# CH32V205RCT-R0.net
KiCad netlist of a schematic drawn in Altium Designer
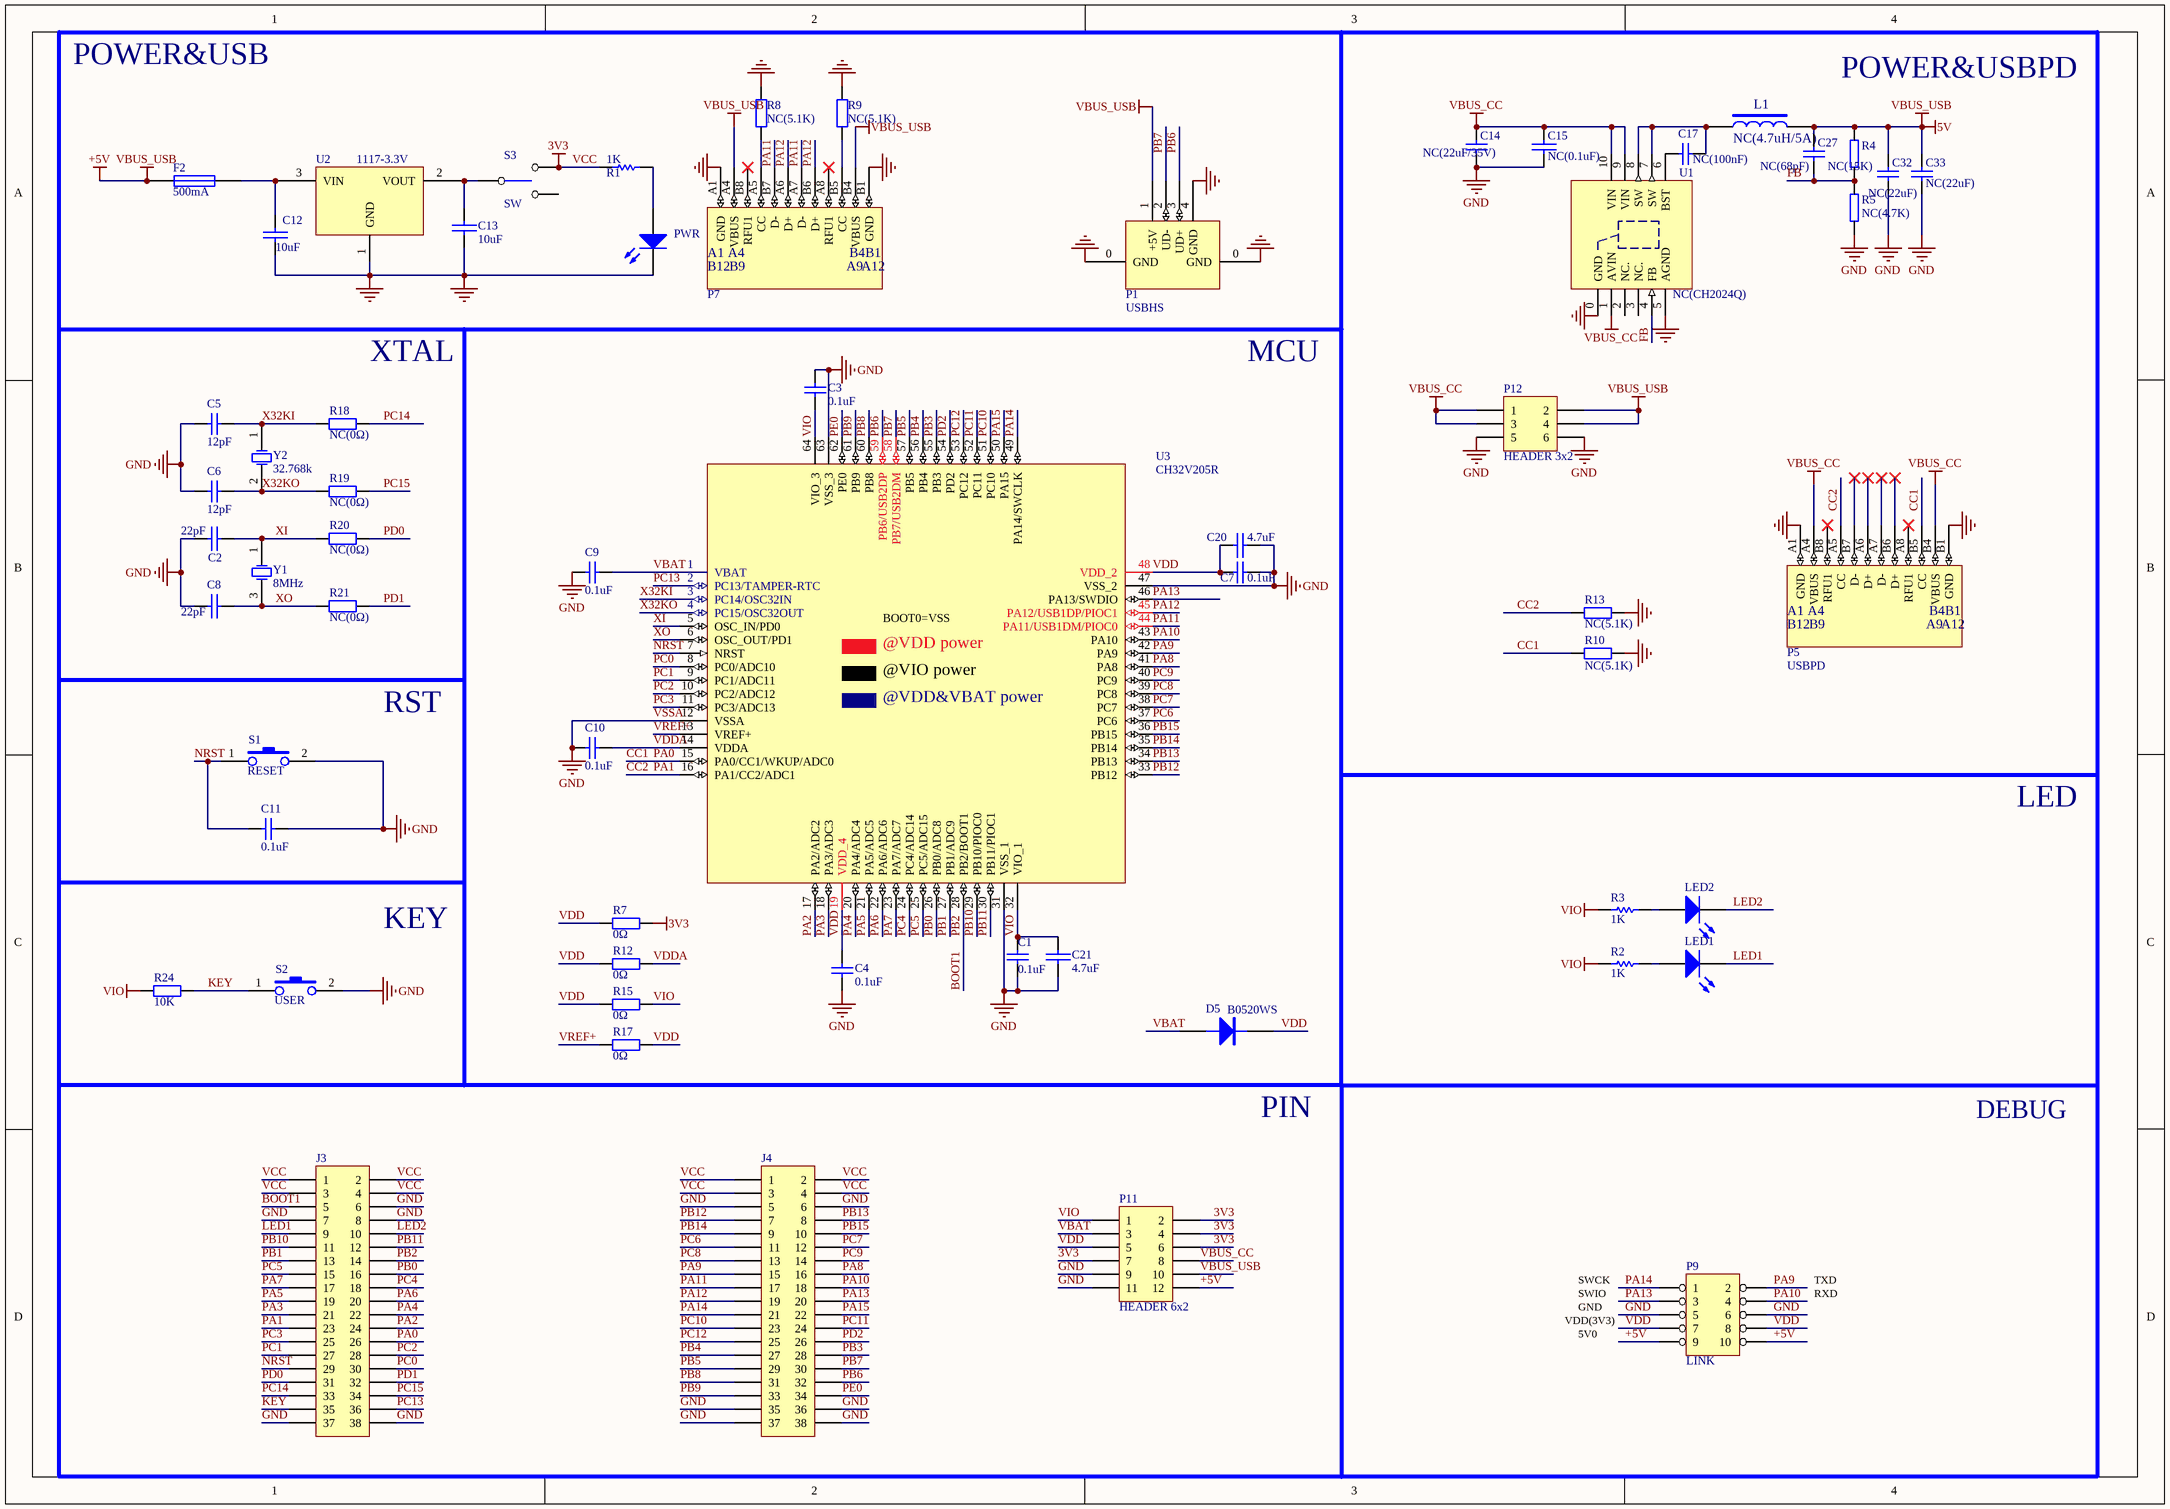
[diagram p0: CH32V205RCT-R0.SchDoc]

(export (version "E")
  (design (tool "Eeschema 10.0.6"))
  (components
    (comp (ref "C1")
      (value "0.1uF")
      (footprint "0402_C")
      (description "Capacitor")
      (libsource (lib "Miscellaneous Devices") (part "Cap"))
    )
    (comp (ref "C2")
      (value "22pF")
      (footprint "0402_C")
      (description "Capacitor")
      (libsource (lib "*") (part "CAP"))
    )
    (comp (ref "C3")
      (value "0.1uF")
      (footprint "0402_C")
      (description "Capacitor")
      (libsource (lib "Miscellaneous Devices") (part "Cap"))
    )
    (comp (ref "C4")
      (value "0.1uF")
      (footprint "0402_C")
      (description "Capacitor")
      (libsource (lib "Miscellaneous Devices") (part "Cap"))
    )
    (comp (ref "C5")
      (value "12pF")
      (footprint "0402_C")
      (description "Capacitor")
      (libsource (lib "Miscellaneous Devices") (part "Cap"))
    )
    (comp (ref "C6")
      (value "12pF")
      (footprint "0402_C")
      (description "Capacitor")
      (libsource (lib "Miscellaneous Devices") (part "Cap"))
    )
    (comp (ref "C7")
      (value "0.1uF")
      (footprint "0402_C")
      (description "Capacitor")
      (libsource (lib "Miscellaneous Devices") (part "Cap"))
    )
    (comp (ref "C8")
      (value "22pF")
      (footprint "0402_C")
      (description "Capacitor")
      (libsource (lib "*") (part "CAP"))
    )
    (comp (ref "C9")
      (value "0.1uF")
      (footprint "0402_C")
      (description "Capacitor")
      (libsource (lib "Miscellaneous Devices") (part "Cap"))
    )
    (comp (ref "C10")
      (value "0.1uF")
      (footprint "0402_C")
      (description "Capacitor")
      (libsource (lib "Miscellaneous Devices") (part "Cap"))
    )
    (comp (ref "C11")
      (value "0.1uF")
      (footprint "0402_C")
      (description "Capacitor")
      (libsource (lib "Miscellaneous Devices") (part "Cap"))
    )
    (comp (ref "C12")
      (value "10uF")
      (footprint "0603_C")
      (description "Capacitor")
      (libsource (lib "*") (part "CAP"))
    )
    (comp (ref "C13")
      (value "10uF")
      (footprint "0603_C")
      (description "Capacitor")
      (libsource (lib "*") (part "CAP"))
    )
    (comp (ref "C14")
      (value "NC(22uF/35V)")
      (footprint "0805_C")
      (description "贴片电容")
      (libsource (lib "Miscellaneous Devices LC") (part "0603 100nF (104) 10% 50V"))
    )
    (comp (ref "C15")
      (value "NC(0.1uF)")
      (footprint "0402_C")
      (description "Capacitor")
      (libsource (lib "*") (part "CAP"))
    )
    (comp (ref "C17")
      (value "NC(100nF)")
      (footprint "0402_C")
      (description "贴片电容")
      (libsource (lib "Miscellaneous Devices LC") (part "0603 1uF (105) 10% 50V"))
    )
    (comp (ref "C20")
      (value "4.7uF")
      (footprint "0402_C")
      (description "Capacitor")
      (libsource (lib "*") (part "CAP"))
    )
    (comp (ref "C21")
      (value "4.7uF")
      (footprint "0402_C")
      (description "Capacitor")
      (libsource (lib "*") (part "CAP"))
    )
    (comp (ref "C27")
      (value "NC(68pF)")
      (footprint "0402_C")
      (description "贴片电容")
      (libsource (lib "Miscellaneous Devices LC") (part "0603 100nF (104) 10% 50V"))
    )
    (comp (ref "C32")
      (value "NC(22uF)")
      (footprint "0805_C")
      (description "贴片电容")
      (libsource (lib "Miscellaneous Devices LC") (part "0603 100nF (104) 10% 50V"))
    )
    (comp (ref "C33")
      (value "NC(22uF)")
      (footprint "0805_C")
      (description "贴片电容")
      (libsource (lib "Miscellaneous Devices LC") (part "0603 100nF (104) 10% 50V"))
    )
    (comp (ref "D5")
      (value "B0520WS")
      (footprint "SOD-323")
      (description "Diode")
      (libsource (lib "*") (part "DIODE"))
    )
    (comp (ref "F2")
      (value "500mA")
      (footprint "0603")
      (description "Fuse")
      (libsource (lib "*") (part "FUSE1"))
    )
    (comp (ref "J3")
      (value "Header 19X2")
      (footprint "IDC38-2.54mm")
      (description "Header, 19-Pin, Dual row")
      (fields (field (name "PUBLISHER") "Altium Limited"))
      (libsource (lib "Miscellaneous Connectors") (part "Header 19X2"))
    )
    (comp (ref "J4")
      (value "Header 19X2")
      (footprint "IDC38-2.54mm")
      (description "Header, 19-Pin, Dual row")
      (fields (field (name "PUBLISHER") "Altium Limited"))
      (libsource (lib "Miscellaneous Connectors") (part "Header 19X2"))
    )
    (comp (ref "L1")
      (value "NC(4.7uH/5A)")
      (footprint "IND-SMD_L7.0-W6.6")
      (libsource (lib "wch_sch_others") (part "INDUCTOR"))
    )
    (comp (ref "LED1")
      (value "LED1   blue")
      (footprint "0603+")
      (description "Typical INFRARED GaAs LED")
      (fields (field (name "PUBLISHER") "Altium Limited"))
      (libsource (lib "Miscellaneous Devices") (part "LED0"))
    )
    (comp (ref "LED2")
      (value "LED2  blue")
      (footprint "0603+")
      (description "Typical INFRARED GaAs LED")
      (fields (field (name "PUBLISHER") "Altium Limited"))
      (libsource (lib "Miscellaneous Devices") (part "LED0"))
    )
    (comp (ref "P1")
      (value "USBHS")
      (footprint "USBAF")
      (description "USB Port")
      (libsource (lib "*") (part "USB"))
    )
    (comp (ref "P5")
      (value "USBPD")
      (footprint "TYPE-C-Receptacle-2.0")
      (libsource (lib "*") (part "TYPE-C1"))
    )
    (comp (ref "P7")
      (value "TYPE-C")
      (footprint "TYPE-C-Receptacle-2.0")
      (libsource (lib "*") (part "TYPE-C1"))
    )
    (comp (ref "P9")
      (value "LINK")
      (footprint "MYPCB:IDC10-2.54mm")
      (description "Header, 5-Pin, Dual row")
      (libsource (lib "wch_sch_others") (part "HEADER 5x2"))
    )
    (comp (ref "P11")
      (value "HEADER 6x2")
      (footprint "MYPCB:IDC12-2.54mm")
      (description "Header, 6-Pin, Dual row")
      (libsource (lib "wch_sch_others") (part "HEADER 6x2"))
    )
    (comp (ref "P12")
      (value "HEADER 3x2")
      (footprint "MYPCB:IDC6-2.54mm")
      (description "Header, 3-Pin, Dual row")
      (libsource (lib "wch_sch_others") (part "HEADER 3x2"))
    )
    (comp (ref "PWR")
      (value "POWER  red")
      (footprint "0603+")
      (description "Typical INFRARED GaAs LED")
      (fields (field (name "PUBLISHER") "Altium Limited"))
      (libsource (lib "Miscellaneous Devices") (part "LED0"))
    )
    (comp (ref "R1")
      (value "1K")
      (footprint "0402")
      (description "Semiconductor Resistor")
      (libsource (lib "Miscellaneous Devices") (part "Res Semi"))
    )
    (comp (ref "R2")
      (value "1K")
      (footprint "0402")
      (description "Semiconductor Resistor")
      (libsource (lib "Miscellaneous Devices") (part "Res Semi"))
    )
    (comp (ref "R3")
      (value "1K")
      (footprint "0402")
      (description "Semiconductor Resistor")
      (libsource (lib "Miscellaneous Devices") (part "Res Semi"))
    )
    (comp (ref "R4") (value "NC(15K)") (footprint "0402") (libsource (lib "wch_sch_others(1)") (part "RES")))
    (comp (ref "R5") (value "NC(4.7K)") (footprint "0402") (libsource (lib "wch_sch_others(1)") (part "RES")))
    (comp (ref "R7")
      (value "0Ω")
      (footprint "0402")
      (description "Resistor")
      (libsource (lib "Miscellaneous Devices") (part "Res2"))
    )
    (comp (ref "R8")
      (value "NC(5.1K)")
      (footprint "0402")
      (description "Resistor")
      (libsource (lib "") (part "Res2_1"))
    )
    (comp (ref "R9")
      (value "NC(5.1K)")
      (footprint "0402")
      (description "Resistor")
      (libsource (lib "") (part "Res2_1"))
    )
    (comp (ref "R10")
      (value "NC(5.1K)")
      (footprint "0402")
      (description "Resistor")
      (libsource (lib "") (part "Res2_2"))
    )
    (comp (ref "R12")
      (value "0Ω")
      (footprint "0402")
      (description "Resistor")
      (libsource (lib "Miscellaneous Devices") (part "Res2"))
    )
    (comp (ref "R13")
      (value "NC(5.1K)")
      (footprint "0402")
      (description "Resistor")
      (libsource (lib "") (part "Res2_2"))
    )
    (comp (ref "R15")
      (value "0Ω")
      (footprint "0402")
      (description "Resistor")
      (libsource (lib "Miscellaneous Devices") (part "Res2"))
    )
    (comp (ref "R17")
      (value "0Ω")
      (footprint "0402")
      (description "Resistor")
      (libsource (lib "Miscellaneous Devices") (part "Res2"))
    )
    (comp (ref "R18")
      (value "NC(0Ω)")
      (footprint "0402")
      (description "Resistor")
      (libsource (lib "") (part "Res2_2"))
    )
    (comp (ref "R19")
      (value "NC(0Ω)")
      (footprint "0402")
      (description "Resistor")
      (libsource (lib "Miscellaneous Devices") (part "Res2"))
    )
    (comp (ref "R20")
      (value "NC(0Ω)")
      (footprint "0402")
      (description "Resistor")
      (libsource (lib "Miscellaneous Devices") (part "Res2"))
    )
    (comp (ref "R21")
      (value "NC(0Ω)")
      (footprint "0402")
      (description "Resistor")
      (libsource (lib "Miscellaneous Devices") (part "Res2"))
    )
    (comp (ref "R24")
      (value "10K")
      (footprint "0402")
      (description "Resistor")
      (libsource (lib "Miscellaneous Devices") (part "Res2"))
    )
    (comp (ref "S1")
      (value "RESET")
      (footprint "SMD_6.1x3.65x2.5mm-KEY")
      (libsource (lib "wch_sch_others") (part "KEY1"))
    )
    (comp (ref "S2")
      (value "USER")
      (footprint "SMD_6.1x3.65x2.5mm-KEY")
      (libsource (lib "wch_sch_others") (part "KEY1"))
    )
    (comp (ref "S3") (value "SW") (footprint "SW1") (libsource (lib "MYSCH") (part "SW")))
    (comp (ref "U1")
      (value "NC(CH2024Q)")
      (footprint "DFN10_3X3")
      (description "Step-Down DC-DC Converter, 28V input, FB 1.2V, 3A output")
      (libsource (lib "DHXXXSCH") (part "CH2024Q"))
    )
    (comp (ref "U2")
      (value "1117-3.3V")
      (footprint "SOT-223")
      (libsource (lib "wch_sch_others") (part "1117-3.3V"))
    )
    (comp (ref "U3")
      (value "CH32V205R")
      (footprint "LQFP64_7X7")
      (description "RISC-V MCU, 192MHz, USB_480M, USB FS, PD, PIOC, ADC, TKEY, 2*OPA, 2*CMP")
      (libsource (lib "CHXXX") (part "CH32V205R"))
    )
    (comp (ref "Y1")
      (value "8MHz")
      (footprint "XT3225")
      (description "Crystal Oscillator")
      (fields (field (name "PUBLISHER") "Altium Limited"))
      (libsource (lib "*") (part "XTAL"))
    )
    (comp (ref "Y2")
      (value "32.768k")
      (footprint "FC-135")
      (description "Crystal Oscillator")
      (fields (field (name "PUBLISHER") "Altium Limited"))
      (libsource (lib "Miscellaneous Devices") (part "XTAL"))
    )
  )
  (nets
    (net (code "1") (name "+5V") (class "Default")
      (node (ref "C27") (pin "1") (pinfunction "1_1") (pintype "passive"))
      (node (ref "C32") (pin "2") (pinfunction "2_2") (pintype "passive"))
      (node (ref "C33") (pin "2") (pinfunction "2_2") (pintype "passive"))
      (node (ref "F2") (pin "1") (pinfunction "1_1") (pintype "passive"))
      (node (ref "L1") (pin "2") (pinfunction "2_2") (pintype "passive"))
      (node (ref "P1") (pin "1") (pinfunction "+5V_1") (pintype "power_in"))
      (node (ref "P11") (pin "10") (pinfunction "10_10") (pintype "passive"))
      (node (ref "P11") (pin "12") (pinfunction "12_12") (pintype "passive"))
      (node (ref "P12") (pin "2") (pinfunction "2_2") (pintype "passive"))
      (node (ref "P12") (pin "4") (pinfunction "4_4") (pintype "passive"))
      (node (ref "P7") (pin "A4") (pinfunction "VBUS_A4") (pintype "bidirectional"))
      (node (ref "P7") (pin "B4") (pinfunction "VBUS_B4") (pintype "bidirectional"))
      (node (ref "P9") (pin "10") (pinfunction "10_10") (pintype "passive"))
      (node (ref "P9") (pin "9") (pinfunction "9_9") (pintype "passive"))
      (node (ref "R4") (pin "2") (pintype "passive"))
    )
    (net (code "3") (name "/BOOT1") (class "Default")
      (node (ref "J3") (pin "14") (pinfunction "14_14") (pintype "passive"))
      (node (ref "J3") (pin "5") (pinfunction "5_5") (pintype "passive"))
      (node (ref "U3") (pin "28") (pinfunction "PB2/BOOT1_28") (pintype "bidirectional"))
    )
    (net (code "4") (name "/CC1") (class "Default")
      (node (ref "J3") (pin "26") (pinfunction "26_26") (pintype "passive"))
      (node (ref "P5") (pin "B5") (pinfunction "CC_B5") (pintype "bidirectional"))
      (node (ref "R10") (pin "1") (pinfunction "1_1") (pintype "passive"))
      (node (ref "U3") (pin "15") (pinfunction "PA0/CC1/WKUP/ADC0_15") (pintype "bidirectional"))
    )
    (net (code "5") (name "/CC2") (class "Default")
      (node (ref "J3") (pin "23") (pinfunction "23_23") (pintype "passive"))
      (node (ref "P5") (pin "A5") (pinfunction "CC_A5") (pintype "bidirectional"))
      (node (ref "R13") (pin "1") (pinfunction "1_1") (pintype "passive"))
      (node (ref "U3") (pin "16") (pinfunction "PA1/CC2/ADC1_16") (pintype "bidirectional"))
    )
    (net (code "6") (name "/FB") (class "Default")
      (node (ref "C27") (pin "2") (pinfunction "2_2") (pintype "passive"))
      (node (ref "R4") (pin "1") (pintype "passive"))
      (node (ref "R5") (pin "2") (pintype "passive"))
      (node (ref "U1") (pin "4") (pinfunction "FB_4") (pintype "input"))
    )
    (net (code "7") (name "/KEY") (class "Default")
      (node (ref "J3") (pin "35") (pinfunction "35_35") (pintype "passive"))
      (node (ref "R24") (pin "1") (pinfunction "1_1") (pintype "passive"))
      (node (ref "S2") (pin "1") (pinfunction "1_1") (pintype "passive"))
    )
    (net (code "8") (name "/LED1") (class "Default")
      (node (ref "J3") (pin "9") (pinfunction "9_9") (pintype "passive"))
      (node (ref "LED1") (pin "2") (pinfunction "K_2") (pintype "passive"))
    )
    (net (code "9") (name "/LED2") (class "Default")
      (node (ref "J3") (pin "10") (pinfunction "10_10") (pintype "passive"))
      (node (ref "LED2") (pin "2") (pinfunction "K_2") (pintype "passive"))
    )
    (net (code "10") (name "/NRST") (class "Default")
      (node (ref "C11") (pin "2") (pinfunction "2_2") (pintype "passive"))
      (node (ref "J3") (pin "29") (pinfunction "29_29") (pintype "passive"))
      (node (ref "S1") (pin "1") (pinfunction "1_1") (pintype "passive"))
      (node (ref "U3") (pin "7") (pinfunction "NRST_7") (pintype "input"))
    )
    (net (code "11") (name "/PA2") (class "Default")
      (node (ref "J3") (pin "24") (pinfunction "24_24") (pintype "passive"))
      (node (ref "U3") (pin "17") (pinfunction "PA2/ADC2_17") (pintype "bidirectional"))
    )
    (net (code "12") (name "/PA3") (class "Default")
      (node (ref "J3") (pin "21") (pinfunction "21_21") (pintype "passive"))
      (node (ref "U3") (pin "18") (pinfunction "PA3/ADC3_18") (pintype "bidirectional"))
    )
    (net (code "13") (name "/PA4") (class "Default")
      (node (ref "J3") (pin "22") (pinfunction "22_22") (pintype "passive"))
      (node (ref "U3") (pin "20") (pinfunction "PA4/ADC4_20") (pintype "bidirectional"))
    )
    (net (code "14") (name "/PA5") (class "Default")
      (node (ref "J3") (pin "19") (pinfunction "19_19") (pintype "passive"))
      (node (ref "U3") (pin "21") (pinfunction "PA5/ADC5_21") (pintype "bidirectional"))
    )
    (net (code "15") (name "/PA6") (class "Default")
      (node (ref "J3") (pin "20") (pinfunction "20_20") (pintype "passive"))
      (node (ref "U3") (pin "22") (pinfunction "PA6/ADC6_22") (pintype "bidirectional"))
    )
    (net (code "16") (name "/PA7") (class "Default")
      (node (ref "J3") (pin "17") (pinfunction "17_17") (pintype "passive"))
      (node (ref "U3") (pin "23") (pinfunction "PA7/ADC7_23") (pintype "bidirectional"))
    )
    (net (code "17") (name "/PA8") (class "Default")
      (node (ref "J4") (pin "16") (pinfunction "16_16") (pintype "passive"))
      (node (ref "U3") (pin "41") (pinfunction "PA8_41") (pintype "bidirectional"))
    )
    (net (code "18") (name "/PA9") (class "Default")
      (node (ref "J4") (pin "15") (pinfunction "15_15") (pintype "passive"))
      (node (ref "P9") (pin "2") (pinfunction "2_2") (pintype "passive"))
      (node (ref "U3") (pin "42") (pinfunction "PA9_42") (pintype "bidirectional"))
    )
    (net (code "19") (name "/PA10") (class "Default")
      (node (ref "J4") (pin "18") (pinfunction "18_18") (pintype "passive"))
      (node (ref "P9") (pin "4") (pinfunction "4_4") (pintype "passive"))
      (node (ref "U3") (pin "43") (pinfunction "PA10_43") (pintype "bidirectional"))
    )
    (net (code "20") (name "/PA11") (class "Default")
      (node (ref "J4") (pin "17") (pinfunction "17_17") (pintype "passive"))
      (node (ref "P7") (pin "A7") (pinfunction "D-_A7") (pintype "bidirectional"))
      (node (ref "P7") (pin "B7") (pinfunction "D-_B7") (pintype "bidirectional"))
      (node (ref "U3") (pin "44") (pinfunction "PA11/USB1DM/PIOC0_44") (pintype "bidirectional"))
    )
    (net (code "21") (name "/PA12") (class "Default")
      (node (ref "J4") (pin "19") (pinfunction "19_19") (pintype "passive"))
      (node (ref "P7") (pin "A6") (pinfunction "D+_A6") (pintype "bidirectional"))
      (node (ref "P7") (pin "B6") (pinfunction "D+_B6") (pintype "bidirectional"))
      (node (ref "U3") (pin "45") (pinfunction "PA12/USB1DP/PIOC1_45") (pintype "bidirectional"))
    )
    (net (code "22") (name "/PA13") (class "Default")
      (node (ref "J4") (pin "20") (pinfunction "20_20") (pintype "passive"))
      (node (ref "P9") (pin "3") (pinfunction "3_3") (pintype "passive"))
      (node (ref "U3") (pin "46") (pinfunction "PA13/SWDIO_46") (pintype "bidirectional"))
    )
    (net (code "23") (name "/PA14") (class "Default")
      (node (ref "J4") (pin "21") (pinfunction "21_21") (pintype "passive"))
      (node (ref "P9") (pin "1") (pinfunction "1_1") (pintype "passive"))
      (node (ref "U3") (pin "49") (pinfunction "PA14/SWCLK_49") (pintype "bidirectional"))
    )
    (net (code "24") (name "/PA15") (class "Default")
      (node (ref "J4") (pin "22") (pinfunction "22_22") (pintype "passive"))
      (node (ref "U3") (pin "50") (pinfunction "PA15_50") (pintype "bidirectional"))
    )
    (net (code "25") (name "/PB0") (class "Default")
      (node (ref "J3") (pin "16") (pinfunction "16_16") (pintype "passive"))
      (node (ref "U3") (pin "26") (pinfunction "PB0/ADC8_26") (pintype "bidirectional"))
    )
    (net (code "26") (name "/PB1") (class "Default")
      (node (ref "J3") (pin "13") (pinfunction "13_13") (pintype "passive"))
      (node (ref "U3") (pin "27") (pinfunction "PB1/ADC9_27") (pintype "bidirectional"))
    )
    (net (code "27") (name "/PB3") (class "Default")
      (node (ref "J4") (pin "28") (pinfunction "28_28") (pintype "passive"))
      (node (ref "U3") (pin "55") (pinfunction "PB3_55") (pintype "bidirectional"))
    )
    (net (code "28") (name "/PB4") (class "Default")
      (node (ref "J4") (pin "27") (pinfunction "27_27") (pintype "passive"))
      (node (ref "U3") (pin "56") (pinfunction "PB4_56") (pintype "bidirectional"))
    )
    (net (code "29") (name "/PB5") (class "Default")
      (node (ref "J4") (pin "29") (pinfunction "29_29") (pintype "passive"))
      (node (ref "U3") (pin "57") (pinfunction "PB5_57") (pintype "bidirectional"))
    )
    (net (code "30") (name "/PB6") (class "Default")
      (node (ref "J4") (pin "32") (pinfunction "32_32") (pintype "passive"))
      (node (ref "P1") (pin "3") (pinfunction "UD+_3") (pintype "bidirectional"))
      (node (ref "U3") (pin "59") (pinfunction "PB6/USB2DP_59") (pintype "bidirectional"))
    )
    (net (code "31") (name "/PB7") (class "Default")
      (node (ref "J4") (pin "30") (pinfunction "30_30") (pintype "passive"))
      (node (ref "P1") (pin "2") (pinfunction "UD-_2") (pintype "bidirectional"))
      (node (ref "U3") (pin "58") (pinfunction "PB7/USB2DM_58") (pintype "bidirectional"))
    )
    (net (code "32") (name "/PB8") (class "Default")
      (node (ref "J4") (pin "31") (pinfunction "31_31") (pintype "passive"))
      (node (ref "U3") (pin "60") (pinfunction "PB8_60") (pintype "bidirectional"))
    )
    (net (code "33") (name "/PB9") (class "Default")
      (node (ref "J4") (pin "33") (pinfunction "33_33") (pintype "passive"))
      (node (ref "U3") (pin "61") (pinfunction "PB9_61") (pintype "bidirectional"))
    )
    (net (code "34") (name "/PB10") (class "Default")
      (node (ref "J3") (pin "11") (pinfunction "11_11") (pintype "passive"))
      (node (ref "U3") (pin "29") (pinfunction "PB10/PIOC0_29") (pintype "bidirectional"))
    )
    (net (code "35") (name "/PB11") (class "Default")
      (node (ref "J3") (pin "12") (pinfunction "12_12") (pintype "passive"))
      (node (ref "U3") (pin "30") (pinfunction "PB11/PIOC1_30") (pintype "bidirectional"))
    )
    (net (code "36") (name "/PB12") (class "Default")
      (node (ref "J4") (pin "7") (pinfunction "7_7") (pintype "passive"))
      (node (ref "U3") (pin "33") (pinfunction "PB12_33") (pintype "bidirectional"))
    )
    (net (code "37") (name "/PB13") (class "Default")
      (node (ref "J4") (pin "8") (pinfunction "8_8") (pintype "passive"))
      (node (ref "U3") (pin "34") (pinfunction "PB13_34") (pintype "bidirectional"))
    )
    (net (code "38") (name "/PB14") (class "Default")
      (node (ref "J4") (pin "9") (pinfunction "9_9") (pintype "passive"))
      (node (ref "U3") (pin "35") (pinfunction "PB14_35") (pintype "bidirectional"))
    )
    (net (code "39") (name "/PB15") (class "Default")
      (node (ref "J4") (pin "10") (pinfunction "10_10") (pintype "passive"))
      (node (ref "U3") (pin "36") (pinfunction "PB15_36") (pintype "bidirectional"))
    )
    (net (code "40") (name "/PC0") (class "Default")
      (node (ref "J3") (pin "30") (pinfunction "30_30") (pintype "passive"))
      (node (ref "U3") (pin "8") (pinfunction "PC0/ADC10_8") (pintype "bidirectional"))
    )
    (net (code "41") (name "/PC1") (class "Default")
      (node (ref "J3") (pin "27") (pinfunction "27_27") (pintype "passive"))
      (node (ref "U3") (pin "9") (pinfunction "PC1/ADC11_9") (pintype "bidirectional"))
    )
    (net (code "42") (name "/PC2") (class "Default")
      (node (ref "J3") (pin "28") (pinfunction "28_28") (pintype "passive"))
      (node (ref "U3") (pin "10") (pinfunction "PC2/ADC12_10") (pintype "bidirectional"))
    )
    (net (code "43") (name "/PC3") (class "Default")
      (node (ref "J3") (pin "25") (pinfunction "25_25") (pintype "passive"))
      (node (ref "U3") (pin "11") (pinfunction "PC3/ADC13_11") (pintype "bidirectional"))
    )
    (net (code "44") (name "/PC4") (class "Default")
      (node (ref "J3") (pin "18") (pinfunction "18_18") (pintype "passive"))
      (node (ref "U3") (pin "24") (pinfunction "PC4/ADC14_24") (pintype "bidirectional"))
    )
    (net (code "45") (name "/PC5") (class "Default")
      (node (ref "J3") (pin "15") (pinfunction "15_15") (pintype "passive"))
      (node (ref "U3") (pin "25") (pinfunction "PC5/ADC15_25") (pintype "bidirectional"))
    )
    (net (code "46") (name "/PC6") (class "Default")
      (node (ref "J4") (pin "11") (pinfunction "11_11") (pintype "passive"))
      (node (ref "U3") (pin "37") (pinfunction "PC6_37") (pintype "bidirectional"))
    )
    (net (code "47") (name "/PC7") (class "Default")
      (node (ref "J4") (pin "12") (pinfunction "12_12") (pintype "passive"))
      (node (ref "U3") (pin "38") (pinfunction "PC7_38") (pintype "bidirectional"))
    )
    (net (code "48") (name "/PC8") (class "Default")
      (node (ref "J4") (pin "13") (pinfunction "13_13") (pintype "passive"))
      (node (ref "U3") (pin "39") (pinfunction "PC8_39") (pintype "bidirectional"))
    )
    (net (code "49") (name "/PC9") (class "Default")
      (node (ref "J4") (pin "14") (pinfunction "14_14") (pintype "passive"))
      (node (ref "U3") (pin "40") (pinfunction "PC9_40") (pintype "bidirectional"))
    )
    (net (code "50") (name "/PC10") (class "Default")
      (node (ref "J4") (pin "23") (pinfunction "23_23") (pintype "passive"))
      (node (ref "U3") (pin "51") (pinfunction "PC10_51") (pintype "bidirectional"))
    )
    (net (code "51") (name "/PC11") (class "Default")
      (node (ref "J4") (pin "24") (pinfunction "24_24") (pintype "passive"))
      (node (ref "U3") (pin "52") (pinfunction "PC11_52") (pintype "bidirectional"))
    )
    (net (code "52") (name "/PC12") (class "Default")
      (node (ref "J4") (pin "25") (pinfunction "25_25") (pintype "passive"))
      (node (ref "U3") (pin "53") (pinfunction "PC12_53") (pintype "bidirectional"))
    )
    (net (code "53") (name "/PC13") (class "Default")
      (node (ref "J3") (pin "36") (pinfunction "36_36") (pintype "passive"))
      (node (ref "U3") (pin "2") (pinfunction "PC13/TAMPER-RTC_2") (pintype "bidirectional"))
    )
    (net (code "54") (name "/PC14") (class "Default")
      (node (ref "J3") (pin "33") (pinfunction "33_33") (pintype "passive"))
      (node (ref "R18") (pin "2") (pinfunction "2_2") (pintype "passive"))
    )
    (net (code "55") (name "/PC15") (class "Default")
      (node (ref "J3") (pin "34") (pinfunction "34_34") (pintype "passive"))
      (node (ref "R19") (pin "1") (pinfunction "1_1") (pintype "passive"))
    )
    (net (code "56") (name "/PD0") (class "Default")
      (node (ref "J3") (pin "31") (pinfunction "31_31") (pintype "passive"))
      (node (ref "R20") (pin "1") (pinfunction "1_1") (pintype "passive"))
    )
    (net (code "57") (name "/PD1") (class "Default")
      (node (ref "J3") (pin "32") (pinfunction "32_32") (pintype "passive"))
      (node (ref "R21") (pin "1") (pinfunction "1_1") (pintype "passive"))
    )
    (net (code "58") (name "/PD2") (class "Default")
      (node (ref "J4") (pin "26") (pinfunction "26_26") (pintype "passive"))
      (node (ref "U3") (pin "54") (pinfunction "PD2_54") (pintype "bidirectional"))
    )
    (net (code "59") (name "/PE0") (class "Default")
      (node (ref "J4") (pin "34") (pinfunction "34_34") (pintype "passive"))
      (node (ref "U3") (pin "62") (pinfunction "PE0_62") (pintype "bidirectional"))
    )
    (net (code "60") (name "/VBAT") (class "Default")
      (node (ref "C9") (pin "1") (pinfunction "1_1") (pintype "passive"))
      (node (ref "D5") (pin "1") (pinfunction "A_1") (pintype "passive"))
      (node (ref "P11") (pin "3") (pinfunction "3_3") (pintype "passive"))
      (node (ref "U3") (pin "1") (pinfunction "VBAT_1") (pintype "power_in"))
    )
    (net (code "61") (name "/VDD") (class "Default")
      (node (ref "C20") (pin "1") (pinfunction "1_1") (pintype "passive"))
      (node (ref "C4") (pin "2") (pinfunction "2_2") (pintype "passive"))
      (node (ref "C7") (pin "2") (pinfunction "2_2") (pintype "passive"))
      (node (ref "D5") (pin "2") (pinfunction "K_2") (pintype "passive"))
      (node (ref "P11") (pin "5") (pinfunction "5_5") (pintype "passive"))
      (node (ref "P9") (pin "7") (pinfunction "7_7") (pintype "passive"))
      (node (ref "P9") (pin "8") (pinfunction "8_8") (pintype "passive"))
      (node (ref "R12") (pin "2") (pinfunction "2_2") (pintype "passive"))
      (node (ref "R15") (pin "2") (pinfunction "2_2") (pintype "passive"))
      (node (ref "R17") (pin "1") (pinfunction "1_1") (pintype "passive"))
      (node (ref "R7") (pin "2") (pinfunction "2_2") (pintype "passive"))
      (node (ref "U3") (pin "19") (pinfunction "VDD_4_19") (pintype "power_in"))
      (node (ref "U3") (pin "48") (pinfunction "VDD_2_48") (pintype "power_in"))
    )
    (net (code "62") (name "/VDDA") (class "Default")
      (node (ref "C10") (pin "1") (pinfunction "1_1") (pintype "passive"))
      (node (ref "R12") (pin "1") (pinfunction "1_1") (pintype "passive"))
      (node (ref "U3") (pin "14") (pinfunction "VDDA_14") (pintype "power_in"))
    )
    (net (code "63") (name "/VREF+") (class "Default")
      (node (ref "R17") (pin "2") (pinfunction "2_2") (pintype "passive"))
      (node (ref "U3") (pin "13") (pinfunction "VREF+_13") (pintype "power_in"))
    )
    (net (code "64") (name "/X32KI") (class "Default")
      (node (ref "C5") (pin "1") (pinfunction "1_1") (pintype "passive"))
      (node (ref "R18") (pin "1") (pinfunction "1_1") (pintype "passive"))
      (node (ref "U3") (pin "3") (pinfunction "PC14/OSC32IN_3") (pintype "bidirectional"))
      (node (ref "Y2") (pin "1") (pinfunction "OSC1_1") (pintype "passive"))
    )
    (net (code "65") (name "/X32KO") (class "Default")
      (node (ref "C6") (pin "1") (pinfunction "1_1") (pintype "passive"))
      (node (ref "R19") (pin "2") (pinfunction "2_2") (pintype "passive"))
      (node (ref "U3") (pin "4") (pinfunction "PC15/OSC32OUT_4") (pintype "bidirectional"))
      (node (ref "Y2") (pin "2") (pinfunction "OSC2_2") (pintype "passive"))
    )
    (net (code "66") (name "/XI") (class "Default")
      (node (ref "C2") (pin "2") (pinfunction "2_2") (pintype "passive"))
      (node (ref "R20") (pin "2") (pinfunction "2_2") (pintype "passive"))
      (node (ref "U3") (pin "5") (pinfunction "OSC_IN/PD0_5") (pintype "bidirectional"))
      (node (ref "Y1") (pin "1") (pinfunction "OSC1_1") (pintype "passive"))
    )
    (net (code "67") (name "/XO") (class "Default")
      (node (ref "C8") (pin "2") (pinfunction "2_2") (pintype "passive"))
      (node (ref "R21") (pin "2") (pinfunction "2_2") (pintype "passive"))
      (node (ref "U3") (pin "6") (pinfunction "OSC_OUT/PD1_6") (pintype "bidirectional"))
      (node (ref "Y1") (pin "3") (pinfunction "OSC2_3") (pintype "passive"))
    )
    (net (code "68") (name "3V3") (class "Default")
      (node (ref "J3") (pin "1") (pinfunction "1_1") (pintype "passive"))
      (node (ref "J3") (pin "2") (pinfunction "2_2") (pintype "passive"))
      (node (ref "J3") (pin "3") (pinfunction "3_3") (pintype "passive"))
      (node (ref "J3") (pin "4") (pinfunction "4_4") (pintype "passive"))
      (node (ref "J4") (pin "1") (pinfunction "1_1") (pintype "passive"))
      (node (ref "J4") (pin "2") (pinfunction "2_2") (pintype "passive"))
      (node (ref "J4") (pin "3") (pinfunction "3_3") (pintype "passive"))
      (node (ref "J4") (pin "4") (pinfunction "4_4") (pintype "passive"))
      (node (ref "P11") (pin "2") (pinfunction "2_2") (pintype "passive"))
      (node (ref "P11") (pin "4") (pinfunction "4_4") (pintype "passive"))
      (node (ref "P11") (pin "6") (pinfunction "6_6") (pintype "passive"))
      (node (ref "P11") (pin "7") (pinfunction "7_7") (pintype "passive"))
      (node (ref "R1") (pin "2") (pinfunction "2_2") (pintype "passive"))
      (node (ref "R7") (pin "1") (pinfunction "1_1") (pintype "passive"))
      (node (ref "S3") (pin "3") (pinfunction "3_3") (pintype "passive"))
    )
    (net (code "69") (name "GND") (class "Default")
      (node (ref "C1") (pin "1") (pinfunction "1_1") (pintype "passive"))
      (node (ref "C10") (pin "2") (pinfunction "2_2") (pintype "passive"))
      (node (ref "C11") (pin "1") (pinfunction "1_1") (pintype "passive"))
      (node (ref "C12") (pin "2") (pinfunction "2_2") (pintype "passive"))
      (node (ref "C13") (pin "2") (pinfunction "2_2") (pintype "passive"))
      (node (ref "C14") (pin "1") (pinfunction "1_1") (pintype "passive"))
      (node (ref "C15") (pin "1") (pinfunction "1_1") (pintype "passive"))
      (node (ref "C2") (pin "1") (pinfunction "1_1") (pintype "passive"))
      (node (ref "C20") (pin "2") (pinfunction "2_2") (pintype "passive"))
      (node (ref "C21") (pin "1") (pinfunction "1_1") (pintype "passive"))
      (node (ref "C3") (pin "1") (pinfunction "1_1") (pintype "passive"))
      (node (ref "C32") (pin "1") (pinfunction "1_1") (pintype "passive"))
      (node (ref "C33") (pin "1") (pinfunction "1_1") (pintype "passive"))
      (node (ref "C4") (pin "1") (pinfunction "1_1") (pintype "passive"))
      (node (ref "C5") (pin "2") (pinfunction "2_2") (pintype "passive"))
      (node (ref "C6") (pin "2") (pinfunction "2_2") (pintype "passive"))
      (node (ref "C7") (pin "1") (pinfunction "1_1") (pintype "passive"))
      (node (ref "C8") (pin "1") (pinfunction "1_1") (pintype "passive"))
      (node (ref "C9") (pin "2") (pinfunction "2_2") (pintype "passive"))
      (node (ref "J3") (pin "37") (pinfunction "37_37") (pintype "passive"))
      (node (ref "J3") (pin "38") (pinfunction "38_38") (pintype "passive"))
      (node (ref "J3") (pin "6") (pinfunction "6_6") (pintype "passive"))
      (node (ref "J3") (pin "7") (pinfunction "7_7") (pintype "passive"))
      (node (ref "J3") (pin "8") (pinfunction "8_8") (pintype "passive"))
      (node (ref "J4") (pin "35") (pinfunction "35_35") (pintype "passive"))
      (node (ref "J4") (pin "36") (pinfunction "36_36") (pintype "passive"))
      (node (ref "J4") (pin "37") (pinfunction "37_37") (pintype "passive"))
      (node (ref "J4") (pin "38") (pinfunction "38_38") (pintype "passive"))
      (node (ref "J4") (pin "5") (pinfunction "5_5") (pintype "passive"))
      (node (ref "J4") (pin "6") (pinfunction "6_6") (pintype "passive"))
      (node (ref "P1") (pin "0") (pinfunction "GND_0") (pintype "power_in"))
      (node (ref "P1") (pin "4") (pinfunction "GND_4") (pintype "power_in"))
      (node (ref "P11") (pin "11") (pinfunction "11_11") (pintype "passive"))
      (node (ref "P11") (pin "9") (pinfunction "9_9") (pintype "passive"))
      (node (ref "P12") (pin "5") (pinfunction "5_5") (pintype "passive"))
      (node (ref "P12") (pin "6") (pinfunction "6_6") (pintype "passive"))
      (node (ref "P5") (pin "A1") (pinfunction "GND_A1") (pintype "bidirectional"))
      (node (ref "P5") (pin "B1") (pinfunction "GND_B1") (pintype "bidirectional"))
      (node (ref "P7") (pin "A1") (pinfunction "GND_A1") (pintype "bidirectional"))
      (node (ref "P7") (pin "B1") (pinfunction "GND_B1") (pintype "bidirectional"))
      (node (ref "P9") (pin "5") (pinfunction "5_5") (pintype "passive"))
      (node (ref "P9") (pin "6") (pinfunction "6_6") (pintype "passive"))
      (node (ref "PWR") (pin "2") (pinfunction "K_2") (pintype "passive"))
      (node (ref "R10") (pin "2") (pinfunction "2_2") (pintype "passive"))
      (node (ref "R13") (pin "2") (pinfunction "2_2") (pintype "passive"))
      (node (ref "R5") (pin "1") (pintype "passive"))
      (node (ref "R8") (pin "1") (pinfunction "1_1") (pintype "passive"))
      (node (ref "R9") (pin "1") (pinfunction "1_1") (pintype "passive"))
      (node (ref "S1") (pin "2") (pinfunction "2_2") (pintype "passive"))
      (node (ref "S2") (pin "2") (pinfunction "2_2") (pintype "passive"))
      (node (ref "U1") (pin "0") (pinfunction "GND_0") (pintype "power_in"))
      (node (ref "U1") (pin "5") (pinfunction "AGND_5") (pintype "power_in"))
      (node (ref "U2") (pin "1") (pinfunction "GND_1") (pintype "passive"))
      (node (ref "U3") (pin "12") (pinfunction "VSSA_12") (pintype "power_in"))
      (node (ref "U3") (pin "31") (pinfunction "VSS_1_31") (pintype "power_in"))
      (node (ref "U3") (pin "47") (pinfunction "VSS_2_47") (pintype "power_in"))
      (node (ref "U3") (pin "63") (pinfunction "VSS_3_63") (pintype "power_in"))
    )
    (net (code "70") (name "Net-(C17-Pad2)") (class "Default")
      (node (ref "C17") (pin "2") (pinfunction "2_2") (pintype "passive"))
      (node (ref "L1") (pin "1") (pinfunction "1_1") (pintype "passive"))
      (node (ref "U1") (pin "7") (pinfunction "SW_7") (pintype "output"))
      (node (ref "U1") (pin "8") (pinfunction "SW_8") (pintype "output"))
    )
    (net (code "71") (name "Net-(LED1-A)") (class "Default")
      (node (ref "LED1") (pin "1") (pinfunction "A_1") (pintype "passive"))
      (node (ref "R2") (pin "2") (pinfunction "2_2") (pintype "passive"))
    )
    (net (code "72") (name "Net-(LED2-A)") (class "Default")
      (node (ref "LED2") (pin "1") (pinfunction "A_1") (pintype "passive"))
      (node (ref "R3") (pin "2") (pinfunction "2_2") (pintype "passive"))
    )
    (net (code "73") (name "Net-(P7-CC-PadA5)") (class "Default")
      (node (ref "P7") (pin "A5") (pinfunction "CC_A5") (pintype "bidirectional"))
      (node (ref "R8") (pin "2") (pinfunction "2_2") (pintype "passive"))
    )
    (net (code "74") (name "Net-(P7-CC-PadB5)") (class "Default")
      (node (ref "P7") (pin "B5") (pinfunction "CC_B5") (pintype "bidirectional"))
      (node (ref "R9") (pin "2") (pinfunction "2_2") (pintype "passive"))
    )
    (net (code "75") (name "Net-(PWR-A)") (class "Default")
      (node (ref "PWR") (pin "1") (pinfunction "A_1") (pintype "passive"))
      (node (ref "R1") (pin "1") (pinfunction "1_1") (pintype "passive"))
    )
    (net (code "76") (name "Net-(U1-BST)") (class "Default")
      (node (ref "C17") (pin "1") (pinfunction "1_1") (pintype "passive"))
      (node (ref "U1") (pin "6") (pinfunction "BST_6") (pintype "power_in"))
    )
    (net (code "77") (name "Net-(U2-VIN)") (class "Default")
      (node (ref "C12") (pin "1") (pinfunction "1_1") (pintype "passive"))
      (node (ref "F2") (pin "2") (pinfunction "2_2") (pintype "passive"))
      (node (ref "U2") (pin "3") (pinfunction "VIN_3") (pintype "passive"))
    )
    (net (code "78") (name "Net-(U2-VOUT)") (class "Default")
      (node (ref "C13") (pin "1") (pinfunction "1_1") (pintype "passive"))
      (node (ref "S3") (pin "1") (pinfunction "1_1") (pintype "passive"))
      (node (ref "U2") (pin "2") (pinfunction "VOUT_2") (pintype "passive"))
    )
    (net (code "79") (name "VBUS_CC") (class "Default")
      (node (ref "C14") (pin "2") (pinfunction "2_2") (pintype "passive"))
      (node (ref "C15") (pin "2") (pinfunction "2_2") (pintype "passive"))
      (node (ref "P11") (pin "8") (pinfunction "8_8") (pintype "passive"))
      (node (ref "P12") (pin "1") (pinfunction "1_1") (pintype "passive"))
      (node (ref "P12") (pin "3") (pinfunction "3_3") (pintype "passive"))
      (node (ref "P5") (pin "A4") (pinfunction "VBUS_A4") (pintype "bidirectional"))
      (node (ref "P5") (pin "B4") (pinfunction "VBUS_B4") (pintype "bidirectional"))
      (node (ref "U1") (pin "1") (pinfunction "AVIN_1") (pintype "power_in"))
      (node (ref "U1") (pin "10") (pinfunction "VIN_10") (pintype "power_in"))
      (node (ref "U1") (pin "9") (pinfunction "VIN_9") (pintype "power_in"))
    )
    (net (code "80") (name "VIO") (class "Default")
      (node (ref "C1") (pin "2") (pinfunction "2_2") (pintype "passive"))
      (node (ref "C21") (pin "2") (pinfunction "2_2") (pintype "passive"))
      (node (ref "C3") (pin "2") (pinfunction "2_2") (pintype "passive"))
      (node (ref "P11") (pin "1") (pinfunction "1_1") (pintype "passive"))
      (node (ref "R15") (pin "1") (pinfunction "1_1") (pintype "passive"))
      (node (ref "R2") (pin "1") (pinfunction "1_1") (pintype "passive"))
      (node (ref "R24") (pin "2") (pinfunction "2_2") (pintype "passive"))
      (node (ref "R3") (pin "1") (pinfunction "1_1") (pintype "passive"))
      (node (ref "U3") (pin "32") (pinfunction "VIO_1_32") (pintype "power_in"))
      (node (ref "U3") (pin "64") (pinfunction "VIO_3_64") (pintype "power_in"))
    )
    (net (code "81") (name "unconnected-(P5-D+-PadA6)") (class "Default")
      (node (ref "P5") (pin "A6") (pinfunction "D+_A6") (pintype "bidirectional+no_connect"))
    )
    (net (code "82") (name "unconnected-(P5-D+-PadB6)") (class "Default")
      (node (ref "P5") (pin "B6") (pinfunction "D+_B6") (pintype "bidirectional+no_connect"))
    )
    (net (code "83") (name "unconnected-(P5-D--PadA7)") (class "Default")
      (node (ref "P5") (pin "A7") (pinfunction "D-_A7") (pintype "bidirectional+no_connect"))
    )
    (net (code "84") (name "unconnected-(P5-D--PadB7)") (class "Default")
      (node (ref "P5") (pin "B7") (pinfunction "D-_B7") (pintype "bidirectional+no_connect"))
    )
    (net (code "85") (name "unconnected-(P5-RFU1-PadA8)") (class "Default")
      (node (ref "P5") (pin "A8") (pinfunction "RFU1_A8") (pintype "bidirectional+no_connect"))
    )
    (net (code "86") (name "unconnected-(P5-RFU1-PadB8)") (class "Default")
      (node (ref "P5") (pin "B8") (pinfunction "RFU1_B8") (pintype "bidirectional+no_connect"))
    )
    (net (code "87") (name "unconnected-(P7-RFU1-PadA8)") (class "Default")
      (node (ref "P7") (pin "A8") (pinfunction "RFU1_A8") (pintype "bidirectional+no_connect"))
    )
    (net (code "88") (name "unconnected-(P7-RFU1-PadB8)") (class "Default")
      (node (ref "P7") (pin "B8") (pinfunction "RFU1_B8") (pintype "bidirectional+no_connect"))
    )
    (net (code "89") (name "unconnected-(S3-Pad2)") (class "Default")
      (node (ref "S3") (pin "2") (pinfunction "2_2") (pintype "passive"))
    )
    (net (code "90") (name "unconnected-(U1-NC.-Pad2)") (class "Default")
      (node (ref "U1") (pin "2") (pinfunction "NC._2") (pintype "passive"))
    )
    (net (code "91") (name "unconnected-(U1-NC.-Pad3)") (class "Default")
      (node (ref "U1") (pin "3") (pinfunction "NC._3") (pintype "passive"))
    )
  )
)
